# morse_radio_v1.net
KiCad netlist of a schematic drawn in EAGLE
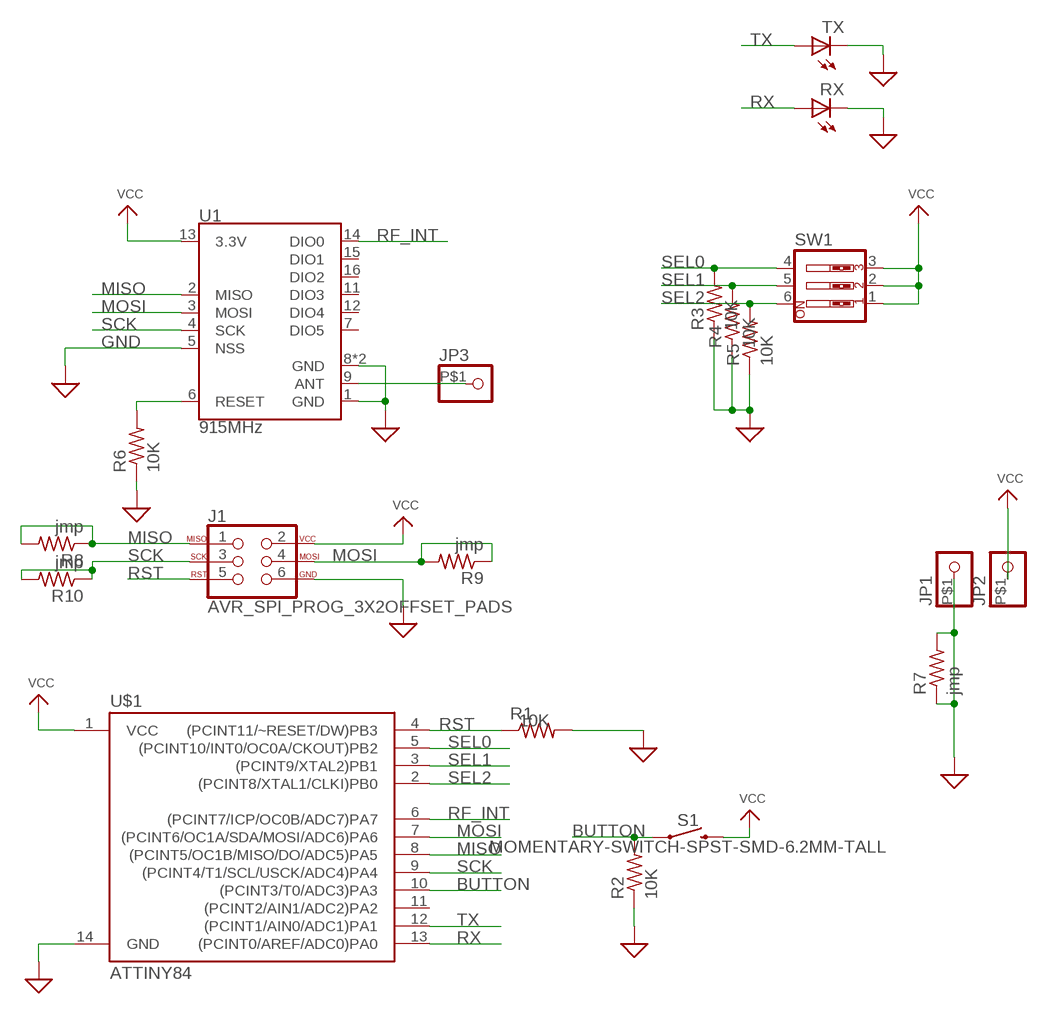
[diagram p0: schematic, sheet 1]

(export (version "E")
  (design (tool "Eeschema 10.0.6"))
  (components
    (comp (ref "J1")
      (value "AVR_SPI_PROG_3X2OFFSET_PADS")
      (footprint "eagle-import:2X3_OFFSET")
      (libsource (lib "eagle-import") (part "AVR_SPI_PROG_3X2OFFSET_PADS"))
    )
    (comp (ref "JP1")
      (value "PINHD-1X1-BIGPOGO")
      (footprint "eagle-import:1X1-BIGPOGO")
      (libsource (lib "eagle-import") (part "PINHD-1X1-BIGPOGO"))
    )
    (comp (ref "JP2")
      (value "PINHD-1X1-BIGPOGO")
      (footprint "eagle-import:1X1-BIGPOGO")
      (libsource (lib "eagle-import") (part "PINHD-1X1-BIGPOGO"))
    )
    (comp (ref "JP3")
      (value "PINHD-1X1-BIGPOGO")
      (footprint "eagle-import:1X1-BIGPOGO")
      (libsource (lib "eagle-import") (part "PINHD-1X1-BIGPOGO"))
    )
    (comp (ref "R1")
      (value "10K")
      (footprint "eagle-import:M1206")
      (libsource (lib "eagle-import") (part "R-US_M1206"))
    )
    (comp (ref "R2")
      (value "10K")
      (footprint "eagle-import:M1206")
      (libsource (lib "eagle-import") (part "R-US_M1206"))
    )
    (comp (ref "R3")
      (value "10K")
      (footprint "eagle-import:M1206")
      (libsource (lib "eagle-import") (part "R-US_M1206"))
    )
    (comp (ref "R4")
      (value "10K")
      (footprint "eagle-import:M1206")
      (libsource (lib "eagle-import") (part "R-US_M1206"))
    )
    (comp (ref "R5")
      (value "10K")
      (footprint "eagle-import:M1206")
      (libsource (lib "eagle-import") (part "R-US_M1206"))
    )
    (comp (ref "R6")
      (value "10K")
      (footprint "eagle-import:M1206")
      (libsource (lib "eagle-import") (part "R-US_M1206"))
    )
    (comp (ref "R7")
      (value "jmp")
      (footprint "eagle-import:M1206")
      (libsource (lib "eagle-import") (part "R-US_M1206"))
    )
    (comp (ref "R8")
      (value "jmp")
      (footprint "eagle-import:M1206")
      (libsource (lib "eagle-import") (part "R-US_M1206"))
    )
    (comp (ref "R9")
      (value "jmp")
      (footprint "eagle-import:M1206")
      (libsource (lib "eagle-import") (part "R-US_M1206"))
    )
    (comp (ref "R10")
      (value "jmp")
      (footprint "eagle-import:M1206")
      (libsource (lib "eagle-import") (part "R-US_M1206"))
    )
    (comp (ref "RX")
      (value "LEDSMT1206")
      (footprint "eagle-import:1206")
      (libsource (lib "eagle-import") (part "LEDSMT1206"))
    )
    (comp (ref "S1")
      (value "MOMENTARY-SWITCH-SPST-SMD-6.2MM-TALL")
      (footprint "eagle-import:TACTILE_SWITCH_SMD_6.2MM_TALL")
      (libsource (lib "eagle-import") (part "MOMENTARY-SWITCH-SPST-SMD-6.2MM-TALL"))
    )
    (comp (ref "SW1")
      (value "SW_DIP-3")
      (footprint "eagle-import:EDG-03")
      (libsource (lib "eagle-import") (part "SW_DIP-3"))
    )
    (comp (ref "TX")
      (value "LEDSMT1206")
      (footprint "eagle-import:1206")
      (libsource (lib "eagle-import") (part "LEDSMT1206"))
    )
    (comp (ref "U$1")
      (value "ATTINY84")
      (footprint "eagle-import:SO14")
      (libsource (lib "eagle-import") (part "ATTINY84"))
    )
    (comp (ref "U1")
      (value "915MHz")
      (footprint "eagle-import:RFM69HCW-XXXS2")
      (libsource (lib "eagle-import") (part "RFM69HCW-915"))
    )
  )
  (nets
    (net (code "1") (name "/BUTTON") (class "Default")
      (node (ref "R2") (pin "2") (pinfunction "2_2") (pintype "passive"))
      (node (ref "S1") (pin "A2") (pinfunction "1_A2") (pintype "passive"))
      (node (ref "U$1") (pin "10") (pinfunction "(PCINT3/T0/ADC3)PA3_10") (pintype "bidirectional"))
    )
    (net (code "2") (name "/MISO") (class "Default")
      (node (ref "J1") (pin "1") (pinfunction "1_1") (pintype "passive"))
      (node (ref "R8") (pin "1") (pinfunction "1_1") (pintype "passive"))
      (node (ref "R8") (pin "2") (pinfunction "2_2") (pintype "passive"))
      (node (ref "U$1") (pin "8") (pinfunction "(PCINT5/OC1B/MISO/DO/ADC5)PA5_8") (pintype "bidirectional"))
      (node (ref "U1") (pin "2") (pinfunction "MISO_2") (pintype "bidirectional"))
    )
    (net (code "3") (name "/MOSI") (class "Default")
      (node (ref "J1") (pin "4") (pinfunction "4_4") (pintype "passive"))
      (node (ref "R9") (pin "1") (pinfunction "1_1") (pintype "passive"))
      (node (ref "R9") (pin "2") (pinfunction "2_2") (pintype "passive"))
      (node (ref "U$1") (pin "7") (pinfunction "(PCINT6/OC1A/SDA/MOSI/ADC6)PA6_7") (pintype "bidirectional"))
      (node (ref "U1") (pin "3") (pinfunction "MOSI_3") (pintype "input"))
    )
    (net (code "4") (name "/RF_INT") (class "Default")
      (node (ref "U$1") (pin "6") (pinfunction "(PCINT7/ICP/OC0B/ADC7)PA7_6") (pintype "bidirectional"))
      (node (ref "U1") (pin "14") (pinfunction "DIO0_14") (pintype "bidirectional"))
    )
    (net (code "5") (name "/RST") (class "Default")
      (node (ref "J1") (pin "5") (pinfunction "5_5") (pintype "passive"))
      (node (ref "R1") (pin "1") (pinfunction "1_1") (pintype "passive"))
      (node (ref "U$1") (pin "4") (pinfunction "(PCINT11/~{RESET/DW})PB3_4") (pintype "bidirectional"))
    )
    (net (code "6") (name "/RX") (class "Default")
      (node (ref "RX") (pin "A") (pinfunction "A_A") (pintype "passive"))
      (node (ref "U$1") (pin "13") (pinfunction "(PCINT0/AREF/ADC0)PA0_13") (pintype "bidirectional"))
    )
    (net (code "7") (name "/SCK") (class "Default")
      (node (ref "J1") (pin "3") (pinfunction "3_3") (pintype "passive"))
      (node (ref "R10") (pin "1") (pinfunction "1_1") (pintype "passive"))
      (node (ref "R10") (pin "2") (pinfunction "2_2") (pintype "passive"))
      (node (ref "U$1") (pin "9") (pinfunction "(PCINT4/T1/SCL/USCK/ADC4)PA4_9") (pintype "bidirectional"))
      (node (ref "U1") (pin "4") (pinfunction "SCK_4") (pintype "input"))
    )
    (net (code "8") (name "/SEL0") (class "Default")
      (node (ref "R3") (pin "2") (pinfunction "2_2") (pintype "passive"))
      (node (ref "SW1") (pin "4") (pinfunction "4_4") (pintype "passive"))
      (node (ref "U$1") (pin "5") (pinfunction "(PCINT10/INT0/OC0A/CKOUT)PB2_5") (pintype "bidirectional"))
    )
    (net (code "9") (name "/SEL1") (class "Default")
      (node (ref "R4") (pin "2") (pinfunction "2_2") (pintype "passive"))
      (node (ref "SW1") (pin "5") (pinfunction "5_5") (pintype "passive"))
      (node (ref "U$1") (pin "3") (pinfunction "(PCINT9/XTAL2)PB1_3") (pintype "bidirectional"))
    )
    (net (code "10") (name "/SEL2") (class "Default")
      (node (ref "R5") (pin "2") (pinfunction "2_2") (pintype "passive"))
      (node (ref "SW1") (pin "6") (pinfunction "6_6") (pintype "passive"))
      (node (ref "U$1") (pin "2") (pinfunction "(PCINT8/XTAL1/CLKI)PB0_2") (pintype "bidirectional"))
    )
    (net (code "11") (name "/TX") (class "Default")
      (node (ref "TX") (pin "A") (pinfunction "A_A") (pintype "passive"))
      (node (ref "U$1") (pin "12") (pinfunction "(PCINT1/AIN0/ADC1)PA1_12") (pintype "bidirectional"))
    )
    (net (code "12") (name "Net-(JP3-1)") (class "Default")
      (node (ref "JP3") (pin "P$1") (pinfunction "1_P$1") (pintype "passive"))
      (node (ref "U1") (pin "9") (pinfunction "ANT_9") (pintype "passive"))
    )
    (net (code "13") (name "Net-(U1-RESET)") (class "Default")
      (node (ref "R6") (pin "2") (pinfunction "2_2") (pintype "passive"))
      (node (ref "U1") (pin "6") (pinfunction "RESET_6") (pintype "input"))
    )
    (net (code "14") (name "SUP") (class "Default")
      (node (ref "J1") (pin "6") (pinfunction "6_6") (pintype "passive"))
      (node (ref "JP1") (pin "P$1") (pinfunction "1_P$1") (pintype "passive"))
      (node (ref "R1") (pin "2") (pinfunction "2_2") (pintype "passive"))
      (node (ref "R2") (pin "1") (pinfunction "1_1") (pintype "passive"))
      (node (ref "R3") (pin "1") (pinfunction "1_1") (pintype "passive"))
      (node (ref "R4") (pin "1") (pinfunction "1_1") (pintype "passive"))
      (node (ref "R5") (pin "1") (pinfunction "1_1") (pintype "passive"))
      (node (ref "R6") (pin "1") (pinfunction "1_1") (pintype "passive"))
      (node (ref "R7") (pin "1") (pinfunction "1_1") (pintype "passive"))
      (node (ref "R7") (pin "2") (pinfunction "2_2") (pintype "passive"))
      (node (ref "RX") (pin "C") (pinfunction "C_C") (pintype "passive"))
      (node (ref "TX") (pin "C") (pinfunction "C_C") (pintype "passive"))
      (node (ref "U$1") (pin "14") (pinfunction "GND_14") (pintype "bidirectional"))
      (node (ref "U1") (pin "1") (pinfunction "GND_1") (pintype "power_in"))
      (node (ref "U1") (pin "10") (pinfunction "GND_10") (pintype "power_in"))
      (node (ref "U1") (pin "5") (pinfunction "NSS_5") (pintype "input"))
      (node (ref "U1") (pin "8") (pinfunction "GND_8") (pintype "power_in"))
    )
    (net (code "15") (name "VCC") (class "Default")
      (node (ref "J1") (pin "2") (pinfunction "2_2") (pintype "passive"))
      (node (ref "JP2") (pin "P$1") (pinfunction "1_P$1") (pintype "passive"))
      (node (ref "S1") (pin "B2") (pinfunction "2_B2") (pintype "passive"))
      (node (ref "SW1") (pin "1") (pinfunction "1_1") (pintype "passive"))
      (node (ref "SW1") (pin "2") (pinfunction "2_2") (pintype "passive"))
      (node (ref "SW1") (pin "3") (pinfunction "3_3") (pintype "passive"))
      (node (ref "U$1") (pin "1") (pinfunction "VCC_1") (pintype "bidirectional"))
      (node (ref "U1") (pin "13") (pinfunction "3.3V_13") (pintype "power_in"))
    )
    (net (code "16") (name "unconnected-(U$1-(PCINT2{slash}AIN1{slash}ADC2)PA2-Pad11)") (class "Default")
      (node (ref "U$1") (pin "11") (pinfunction "(PCINT2/AIN1/ADC2)PA2_11") (pintype "bidirectional"))
    )
    (net (code "17") (name "unconnected-(U1-DIO1-Pad15)") (class "Default")
      (node (ref "U1") (pin "15") (pinfunction "DIO1_15") (pintype "bidirectional"))
    )
    (net (code "18") (name "unconnected-(U1-DIO2-Pad16)") (class "Default")
      (node (ref "U1") (pin "16") (pinfunction "DIO2_16") (pintype "bidirectional"))
    )
    (net (code "19") (name "unconnected-(U1-DIO3-Pad11)") (class "Default")
      (node (ref "U1") (pin "11") (pinfunction "DIO3_11") (pintype "bidirectional"))
    )
    (net (code "20") (name "unconnected-(U1-DIO4-Pad12)") (class "Default")
      (node (ref "U1") (pin "12") (pinfunction "DIO4_12") (pintype "bidirectional"))
    )
    (net (code "21") (name "unconnected-(U1-DIO5-Pad7)") (class "Default")
      (node (ref "U1") (pin "7") (pinfunction "DIO5_7") (pintype "bidirectional"))
    )
  )
)
